# transmisorPCB_2_2.net
KiCad netlist of a schematic drawn in EAGLE
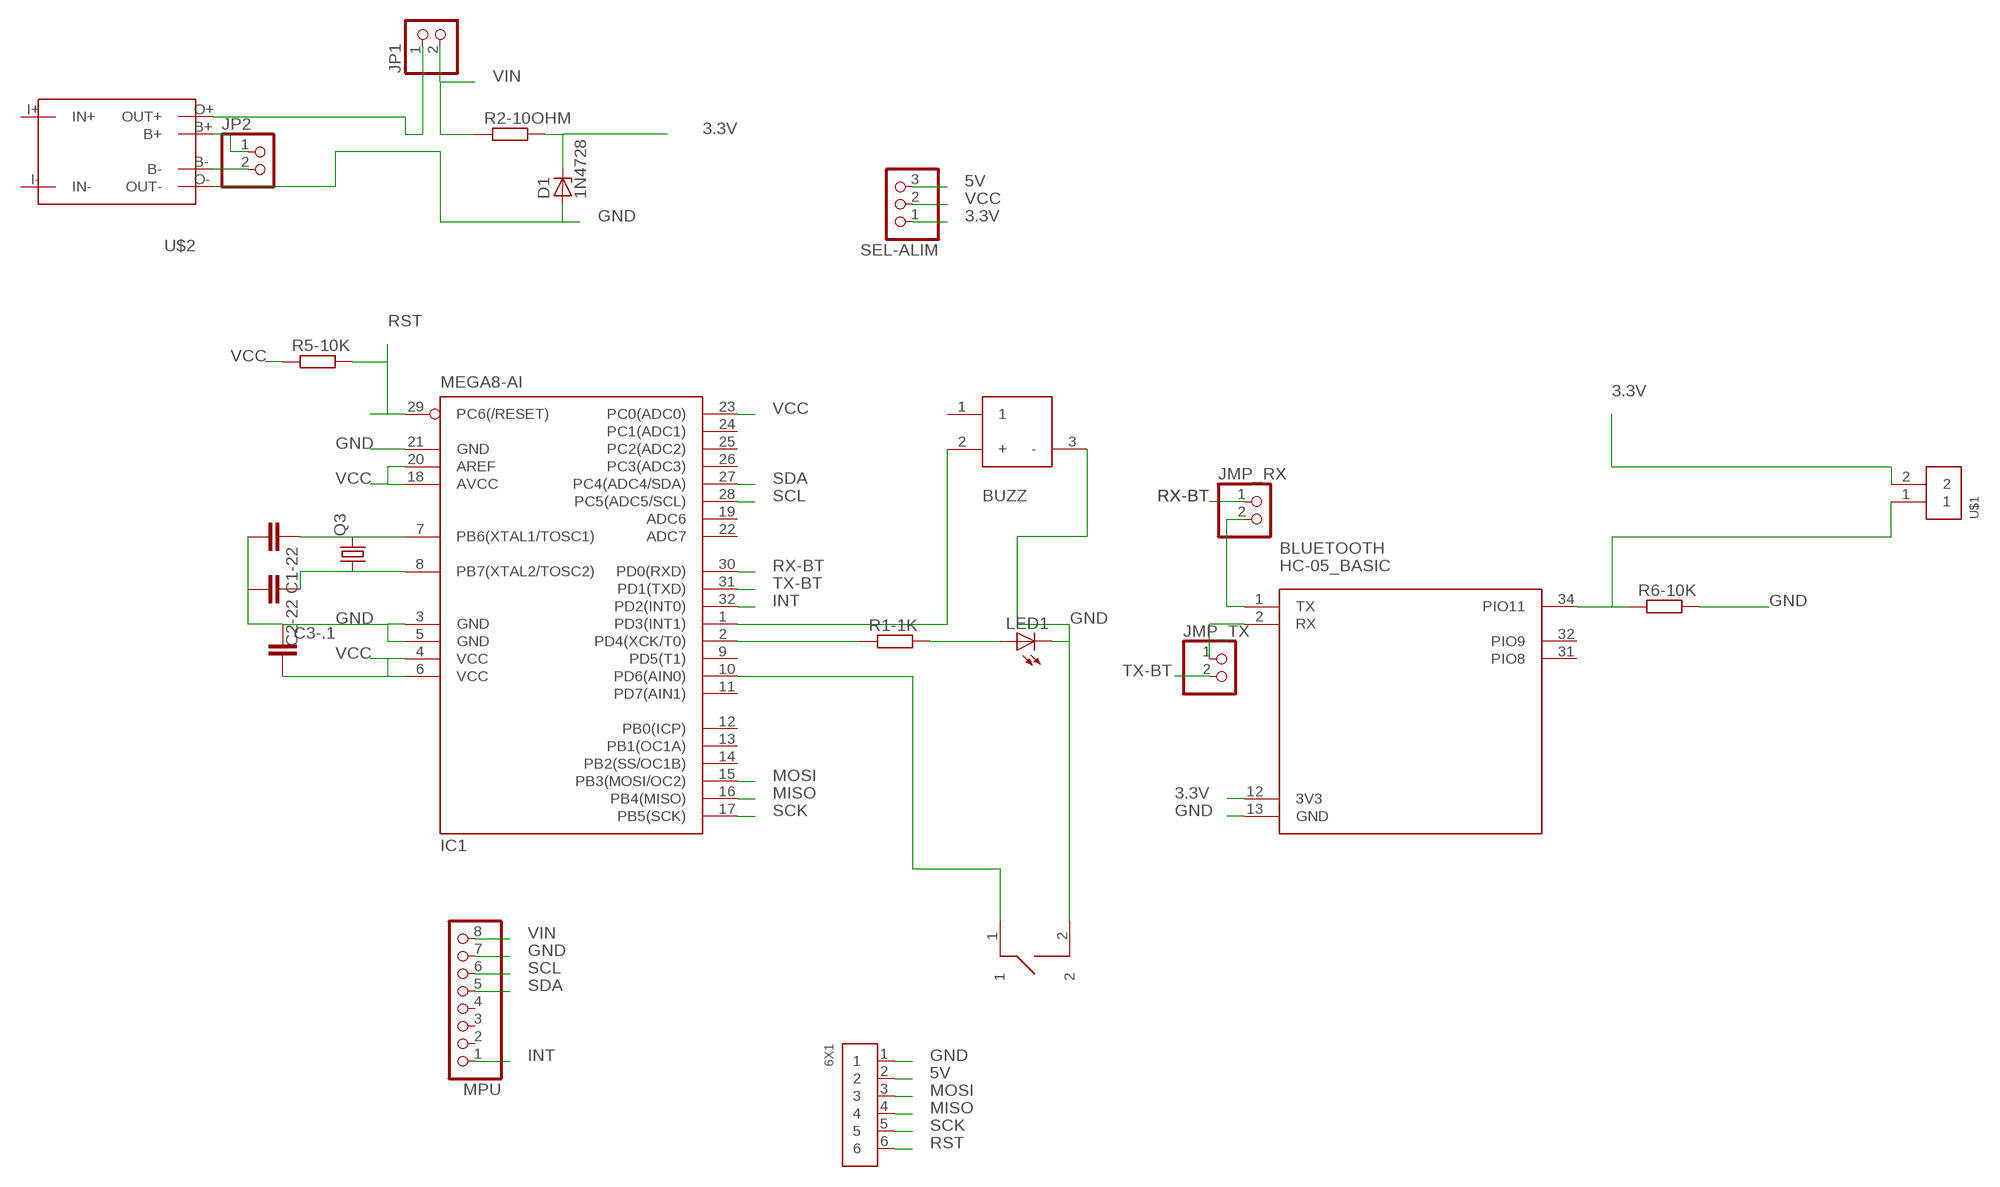
[diagram p0: schematic, sheet 1]

(export (version "E")
  (design (tool "Eeschema 10.0.6"))
  (components
    (comp (ref "6X1")
      (value "PINHEAD_1X6")
      (footprint "eagle-import:PINHEAD_125_1X6")
      (libsource (lib "eagle-import") (part "PINHEAD_1X6"))
    )
    (comp (ref "BLUETOOTH")
      (value "HC-05_BASIC")
      (footprint "eagle-import:BLUETOOTH_SMD")
      (libsource (lib "eagle-import") (part "HC-05_BASIC"))
    )
    (comp (ref "BUZZ")
      (value "SM05ET02A")
      (footprint "eagle-import:SM05ET02A")
      (libsource (lib "eagle-import") (part "SM05ET02A"))
    )
    (comp (ref "C1-22")
      (value "C-EUC0402K")
      (footprint "eagle-import:C0402K")
      (libsource (lib "eagle-import") (part "C-EUC0402K"))
    )
    (comp (ref "C2-22")
      (value "C-EUC0402K")
      (footprint "eagle-import:C0402K")
      (libsource (lib "eagle-import") (part "C-EUC0402K"))
    )
    (comp (ref "C3-.1")
      (value "C-EUC0402K")
      (footprint "eagle-import:C0402K")
      (libsource (lib "eagle-import") (part "C-EUC0402K"))
    )
    (comp (ref "D1")
      (value "1N4728")
      (footprint "eagle-import:DO41Z10")
      (libsource (lib "eagle-import") (part "1N4728"))
    )
    (comp (ref "IC1")
      (value "MEGA8-AI")
      (footprint "eagle-import:TQFP32-08")
      (fields (field (name "MPN") "ATMEGA8-16AU"))
      (libsource (lib "eagle-import") (part "MEGA8-AI"))
    )
    (comp (ref "JMP_RX")
      (value "PINHD-1X2")
      (footprint "eagle-import:1X02")
      (libsource (lib "eagle-import") (part "PINHD-1X2"))
    )
    (comp (ref "JMP_TX")
      (value "PINHD-1X2")
      (footprint "eagle-import:1X02")
      (libsource (lib "eagle-import") (part "PINHD-1X2"))
    )
    (comp (ref "JP1")
      (value "PINHD-1X2")
      (footprint "eagle-import:1X02")
      (libsource (lib "eagle-import") (part "PINHD-1X2"))
    )
    (comp (ref "JP2")
      (value "PINHD-1X2")
      (footprint "eagle-import:1X02")
      (libsource (lib "eagle-import") (part "PINHD-1X2"))
    )
    (comp (ref "LED1")
      (value "LEDCHIPLED-0603-TTW")
      (footprint "eagle-import:CHIPLED-0603-TTW")
      (libsource (lib "eagle-import") (part "LEDCHIPLED-0603-TTW"))
    )
    (comp (ref "MPU")
      (value "PINHD-1X8")
      (footprint "eagle-import:1X08")
      (libsource (lib "eagle-import") (part "PINHD-1X8"))
    )
    (comp (ref "PUSH_OFST")
      (value "PUSH_SMD")
      (footprint "eagle-import:PUSH_SMD")
      (libsource (lib "eagle-import") (part "PUSH_SMD"))
    )
    (comp (ref "Q3")
      (value "CRYSTALHC49U70")
      (footprint "eagle-import:HC49U70")
      (libsource (lib "eagle-import") (part "CRYSTALHC49U70"))
    )
    (comp (ref "R1-1K")
      (value "R-EU_M1206")
      (footprint "eagle-import:M1206")
      (libsource (lib "eagle-import") (part "R-EU_M1206"))
    )
    (comp (ref "R2-10OHM")
      (value "R-EU_R2512")
      (footprint "eagle-import:R2512")
      (libsource (lib "eagle-import") (part "resistor_R-EU_R2512"))
    )
    (comp (ref "R5-10K")
      (value "R-EU_M1206")
      (footprint "eagle-import:M1206")
      (libsource (lib "eagle-import") (part "R-EU_M1206"))
    )
    (comp (ref "R6-10K")
      (value "R-EU_M1206")
      (footprint "eagle-import:M1206")
      (libsource (lib "eagle-import") (part "R-EU_M1206"))
    )
    (comp (ref "SEL-ALIM")
      (value "PINHD-1X3")
      (footprint "eagle-import:1X03")
      (libsource (lib "eagle-import") (part "PINHD-1X3"))
    )
    (comp (ref "U$1")
      (value "CP150_1X2")
      (footprint "eagle-import:CP150_1X2")
      (libsource (lib "eagle-import") (part "CP150_1X2"))
    )
    (comp (ref "U$2")
      (value "TP4056")
      (footprint "eagle-import:TP4056")
      (libsource (lib "eagle-import") (part "TP4056"))
    )
  )
  (nets
    (net (code "1") (name "/3.3V") (class "Default")
      (node (ref "BLUETOOTH") (pin "12") (pinfunction "3V3_12") (pintype "bidirectional"))
      (node (ref "D1") (pin "C") (pinfunction "C_C") (pintype "passive"))
      (node (ref "R2-10OHM") (pin "2") (pinfunction "2_2") (pintype "passive"))
      (node (ref "SEL-ALIM") (pin "1") (pinfunction "1_1") (pintype "passive"))
      (node (ref "U$1") (pin "2") (pinfunction "2_2") (pintype "bidirectional"))
    )
    (net (code "2") (name "/5V") (class "Default")
      (node (ref "6X1") (pin "2") (pinfunction "2_2") (pintype "bidirectional"))
      (node (ref "SEL-ALIM") (pin "3") (pinfunction "3_3") (pintype "passive"))
    )
    (net (code "3") (name "/GND") (class "Default")
      (node (ref "6X1") (pin "1") (pinfunction "1_1") (pintype "bidirectional"))
      (node (ref "BLUETOOTH") (pin "13") (pinfunction "GND_13") (pintype "bidirectional"))
      (node (ref "BUZZ") (pin "3") (pinfunction "-_3") (pintype "bidirectional"))
      (node (ref "C1-22") (pin "2") (pinfunction "2_2") (pintype "passive"))
      (node (ref "C2-22") (pin "2") (pinfunction "2_2") (pintype "passive"))
      (node (ref "C3-.1") (pin "1") (pinfunction "1_1") (pintype "passive"))
      (node (ref "D1") (pin "A") (pinfunction "A_A") (pintype "passive"))
      (node (ref "IC1") (pin "21") (pinfunction "GND_21") (pintype "power_in"))
      (node (ref "IC1") (pin "3") (pinfunction "GND_3") (pintype "power_in"))
      (node (ref "IC1") (pin "5") (pinfunction "GND_5") (pintype "power_in"))
      (node (ref "LED1") (pin "C@1") (pinfunction "C_C@1") (pintype "passive"))
      (node (ref "MPU") (pin "7") (pinfunction "7_7") (pintype "passive"))
      (node (ref "PUSH_OFST") (pin "2") (pinfunction "2_2") (pintype "bidirectional"))
      (node (ref "R6-10K") (pin "2") (pinfunction "2_2") (pintype "passive"))
      (node (ref "U$2") (pin "O-") (pinfunction "OUT-_O-") (pintype "bidirectional"))
    )
    (net (code "4") (name "/INT") (class "Default")
      (node (ref "IC1") (pin "32") (pinfunction "PD2(INT0)_32") (pintype "bidirectional"))
      (node (ref "MPU") (pin "1") (pinfunction "1_1") (pintype "passive"))
    )
    (net (code "5") (name "/MISO") (class "Default")
      (node (ref "6X1") (pin "4") (pinfunction "4_4") (pintype "bidirectional"))
      (node (ref "IC1") (pin "16") (pinfunction "PB4(MISO)_16") (pintype "bidirectional"))
    )
    (net (code "6") (name "/MOSI") (class "Default")
      (node (ref "6X1") (pin "3") (pinfunction "3_3") (pintype "bidirectional"))
      (node (ref "IC1") (pin "15") (pinfunction "PB3(MOSI/OC2)_15") (pintype "bidirectional"))
    )
    (net (code "7") (name "/RST") (class "Default")
      (node (ref "6X1") (pin "6") (pinfunction "6_6") (pintype "bidirectional"))
      (node (ref "IC1") (pin "29") (pinfunction "PC6(/RESET)_29") (pintype "bidirectional"))
      (node (ref "R5-10K") (pin "2") (pinfunction "2_2") (pintype "passive"))
    )
    (net (code "8") (name "/RX-BT") (class "Default")
      (node (ref "IC1") (pin "30") (pinfunction "PD0(RXD)_30") (pintype "bidirectional"))
      (node (ref "JMP_RX") (pin "1") (pinfunction "1_1") (pintype "passive"))
    )
    (net (code "9") (name "/SCK") (class "Default")
      (node (ref "6X1") (pin "5") (pinfunction "5_5") (pintype "bidirectional"))
      (node (ref "IC1") (pin "17") (pinfunction "PB5(SCK)_17") (pintype "bidirectional"))
    )
    (net (code "10") (name "/SCL") (class "Default")
      (node (ref "IC1") (pin "28") (pinfunction "PC5(ADC5/SCL)_28") (pintype "bidirectional"))
      (node (ref "MPU") (pin "6") (pinfunction "6_6") (pintype "passive"))
    )
    (net (code "11") (name "/SDA") (class "Default")
      (node (ref "IC1") (pin "27") (pinfunction "PC4(ADC4/SDA)_27") (pintype "bidirectional"))
      (node (ref "MPU") (pin "5") (pinfunction "5_5") (pintype "passive"))
    )
    (net (code "12") (name "/TX-BT") (class "Default")
      (node (ref "IC1") (pin "31") (pinfunction "PD1(TXD)_31") (pintype "bidirectional"))
      (node (ref "JMP_TX") (pin "2") (pinfunction "2_2") (pintype "passive"))
    )
    (net (code "13") (name "/VCC") (class "Default")
      (node (ref "C3-.1") (pin "2") (pinfunction "2_2") (pintype "passive"))
      (node (ref "IC1") (pin "18") (pinfunction "AVCC_18") (pintype "power_in"))
      (node (ref "IC1") (pin "20") (pinfunction "AREF_20") (pintype "passive"))
      (node (ref "IC1") (pin "23") (pinfunction "PC0(ADC0)_23") (pintype "bidirectional"))
      (node (ref "IC1") (pin "4") (pinfunction "VCC_4") (pintype "power_in"))
      (node (ref "IC1") (pin "6") (pinfunction "VCC_6") (pintype "power_in"))
      (node (ref "R5-10K") (pin "1") (pinfunction "1_1") (pintype "passive"))
      (node (ref "SEL-ALIM") (pin "2") (pinfunction "2_2") (pintype "passive"))
    )
    (net (code "14") (name "/VIN") (class "Default")
      (node (ref "JP1") (pin "2") (pinfunction "2_2") (pintype "passive"))
      (node (ref "MPU") (pin "8") (pinfunction "8_8") (pintype "passive"))
      (node (ref "R2-10OHM") (pin "1") (pinfunction "1_1") (pintype "passive"))
    )
    (net (code "15") (name "Net-(BLUETOOTH-PIO11)") (class "Default")
      (node (ref "BLUETOOTH") (pin "34") (pinfunction "PIO11_34") (pintype "bidirectional"))
      (node (ref "R6-10K") (pin "1") (pinfunction "1_1") (pintype "passive"))
      (node (ref "U$1") (pin "1") (pinfunction "1_1") (pintype "bidirectional"))
    )
    (net (code "16") (name "Net-(BLUETOOTH-RX)") (class "Default")
      (node (ref "BLUETOOTH") (pin "2") (pinfunction "RX_2") (pintype "bidirectional"))
      (node (ref "JMP_TX") (pin "1") (pinfunction "1_1") (pintype "passive"))
    )
    (net (code "17") (name "Net-(BLUETOOTH-TX)") (class "Default")
      (node (ref "BLUETOOTH") (pin "1") (pinfunction "TX_1") (pintype "bidirectional"))
      (node (ref "JMP_RX") (pin "2") (pinfunction "2_2") (pintype "passive"))
    )
    (net (code "18") (name "Net-(BUZZ-+)") (class "Default")
      (node (ref "BUZZ") (pin "2") (pinfunction "+_2") (pintype "bidirectional"))
      (node (ref "IC1") (pin "1") (pinfunction "PD3(INT1)_1") (pintype "bidirectional"))
    )
    (net (code "19") (name "Net-(IC1-PB6(XTAL1{slash}TOSC1))") (class "Default")
      (node (ref "C1-22") (pin "1") (pinfunction "1_1") (pintype "passive"))
      (node (ref "IC1") (pin "7") (pinfunction "PB6(XTAL1/TOSC1)_7") (pintype "bidirectional"))
      (node (ref "Q3") (pin "2") (pinfunction "2_2") (pintype "passive"))
    )
    (net (code "20") (name "Net-(IC1-PB7(XTAL2{slash}TOSC2))") (class "Default")
      (node (ref "C2-22") (pin "1") (pinfunction "1_1") (pintype "passive"))
      (node (ref "IC1") (pin "8") (pinfunction "PB7(XTAL2/TOSC2)_8") (pintype "bidirectional"))
      (node (ref "Q3") (pin "1") (pinfunction "1_1") (pintype "passive"))
    )
    (net (code "21") (name "Net-(IC1-PD4(XCK{slash}T0))") (class "Default")
      (node (ref "IC1") (pin "2") (pinfunction "PD4(XCK/T0)_2") (pintype "bidirectional"))
      (node (ref "R1-1K") (pin "1") (pinfunction "1_1") (pintype "passive"))
    )
    (net (code "22") (name "Net-(IC1-PD6(AIN0))") (class "Default")
      (node (ref "IC1") (pin "10") (pinfunction "PD6(AIN0)_10") (pintype "bidirectional"))
      (node (ref "PUSH_OFST") (pin "1") (pinfunction "1_1") (pintype "bidirectional"))
    )
    (net (code "23") (name "Net-(JP2-Pad1)") (class "Default")
      (node (ref "JP2") (pin "1") (pinfunction "1_1") (pintype "passive"))
      (node (ref "U$2") (pin "B+") (pinfunction "B+_B+") (pintype "bidirectional"))
    )
    (net (code "24") (name "Net-(JP2-Pad2)") (class "Default")
      (node (ref "JP2") (pin "2") (pinfunction "2_2") (pintype "passive"))
      (node (ref "U$2") (pin "B-") (pinfunction "B-_B-") (pintype "bidirectional"))
    )
    (net (code "25") (name "Net-(LED1-A)") (class "Default")
      (node (ref "LED1") (pin "A@1") (pinfunction "A_A@1") (pintype "passive"))
      (node (ref "R1-1K") (pin "2") (pinfunction "2_2") (pintype "passive"))
    )
    (net (code "26") (name "Net-(U$2-OUT+)") (class "Default")
      (node (ref "JP1") (pin "1") (pinfunction "1_1") (pintype "passive"))
      (node (ref "U$2") (pin "O+") (pinfunction "OUT+_O+") (pintype "bidirectional"))
    )
    (net (code "27") (name "unconnected-(BLUETOOTH-PIO8-Pad31)") (class "Default")
      (node (ref "BLUETOOTH") (pin "31") (pinfunction "PIO8_31") (pintype "bidirectional"))
    )
    (net (code "28") (name "unconnected-(BLUETOOTH-PIO9-Pad32)") (class "Default")
      (node (ref "BLUETOOTH") (pin "32") (pinfunction "PIO9_32") (pintype "bidirectional"))
    )
    (net (code "29") (name "unconnected-(BUZZ-Pad1)") (class "Default")
      (node (ref "BUZZ") (pin "1") (pinfunction "1_1") (pintype "bidirectional"))
    )
    (net (code "30") (name "unconnected-(IC1-ADC6-Pad19)") (class "Default")
      (node (ref "IC1") (pin "19") (pinfunction "ADC6_19") (pintype "bidirectional"))
    )
    (net (code "31") (name "unconnected-(IC1-ADC7-Pad22)") (class "Default")
      (node (ref "IC1") (pin "22") (pinfunction "ADC7_22") (pintype "bidirectional"))
    )
    (net (code "32") (name "unconnected-(IC1-PB0(ICP)-Pad12)") (class "Default")
      (node (ref "IC1") (pin "12") (pinfunction "PB0(ICP)_12") (pintype "bidirectional"))
    )
    (net (code "33") (name "unconnected-(IC1-PB1(OC1A)-Pad13)") (class "Default")
      (node (ref "IC1") (pin "13") (pinfunction "PB1(OC1A)_13") (pintype "bidirectional"))
    )
    (net (code "34") (name "unconnected-(IC1-PB2(SS{slash}OC1B)-Pad14)") (class "Default")
      (node (ref "IC1") (pin "14") (pinfunction "PB2(SS/OC1B)_14") (pintype "bidirectional"))
    )
    (net (code "35") (name "unconnected-(IC1-PC1(ADC1)-Pad24)") (class "Default")
      (node (ref "IC1") (pin "24") (pinfunction "PC1(ADC1)_24") (pintype "bidirectional"))
    )
    (net (code "36") (name "unconnected-(IC1-PC2(ADC2)-Pad25)") (class "Default")
      (node (ref "IC1") (pin "25") (pinfunction "PC2(ADC2)_25") (pintype "bidirectional"))
    )
    (net (code "37") (name "unconnected-(IC1-PC3(ADC3)-Pad26)") (class "Default")
      (node (ref "IC1") (pin "26") (pinfunction "PC3(ADC3)_26") (pintype "bidirectional"))
    )
    (net (code "38") (name "unconnected-(IC1-PD5(T1)-Pad9)") (class "Default")
      (node (ref "IC1") (pin "9") (pinfunction "PD5(T1)_9") (pintype "bidirectional"))
    )
    (net (code "39") (name "unconnected-(IC1-PD7(AIN1)-Pad11)") (class "Default")
      (node (ref "IC1") (pin "11") (pinfunction "PD7(AIN1)_11") (pintype "bidirectional"))
    )
    (net (code "40") (name "unconnected-(MPU-Pad2)") (class "Default")
      (node (ref "MPU") (pin "2") (pinfunction "2_2") (pintype "passive"))
    )
    (net (code "41") (name "unconnected-(MPU-Pad3)") (class "Default")
      (node (ref "MPU") (pin "3") (pinfunction "3_3") (pintype "passive"))
    )
    (net (code "42") (name "unconnected-(MPU-Pad4)") (class "Default")
      (node (ref "MPU") (pin "4") (pinfunction "4_4") (pintype "passive"))
    )
    (net (code "43") (name "unconnected-(U$2-IN+-PadI+)") (class "Default")
      (node (ref "U$2") (pin "I+") (pinfunction "IN+_I+") (pintype "bidirectional"))
    )
    (net (code "44") (name "unconnected-(U$2-IN--PadI-)") (class "Default")
      (node (ref "U$2") (pin "I-") (pinfunction "IN-_I-") (pintype "bidirectional"))
    )
  )
)
